# SW6106_A_A_B_C_Lighting_MCU_SEG.net
KiCad netlist of a schematic drawn in Altium Designer
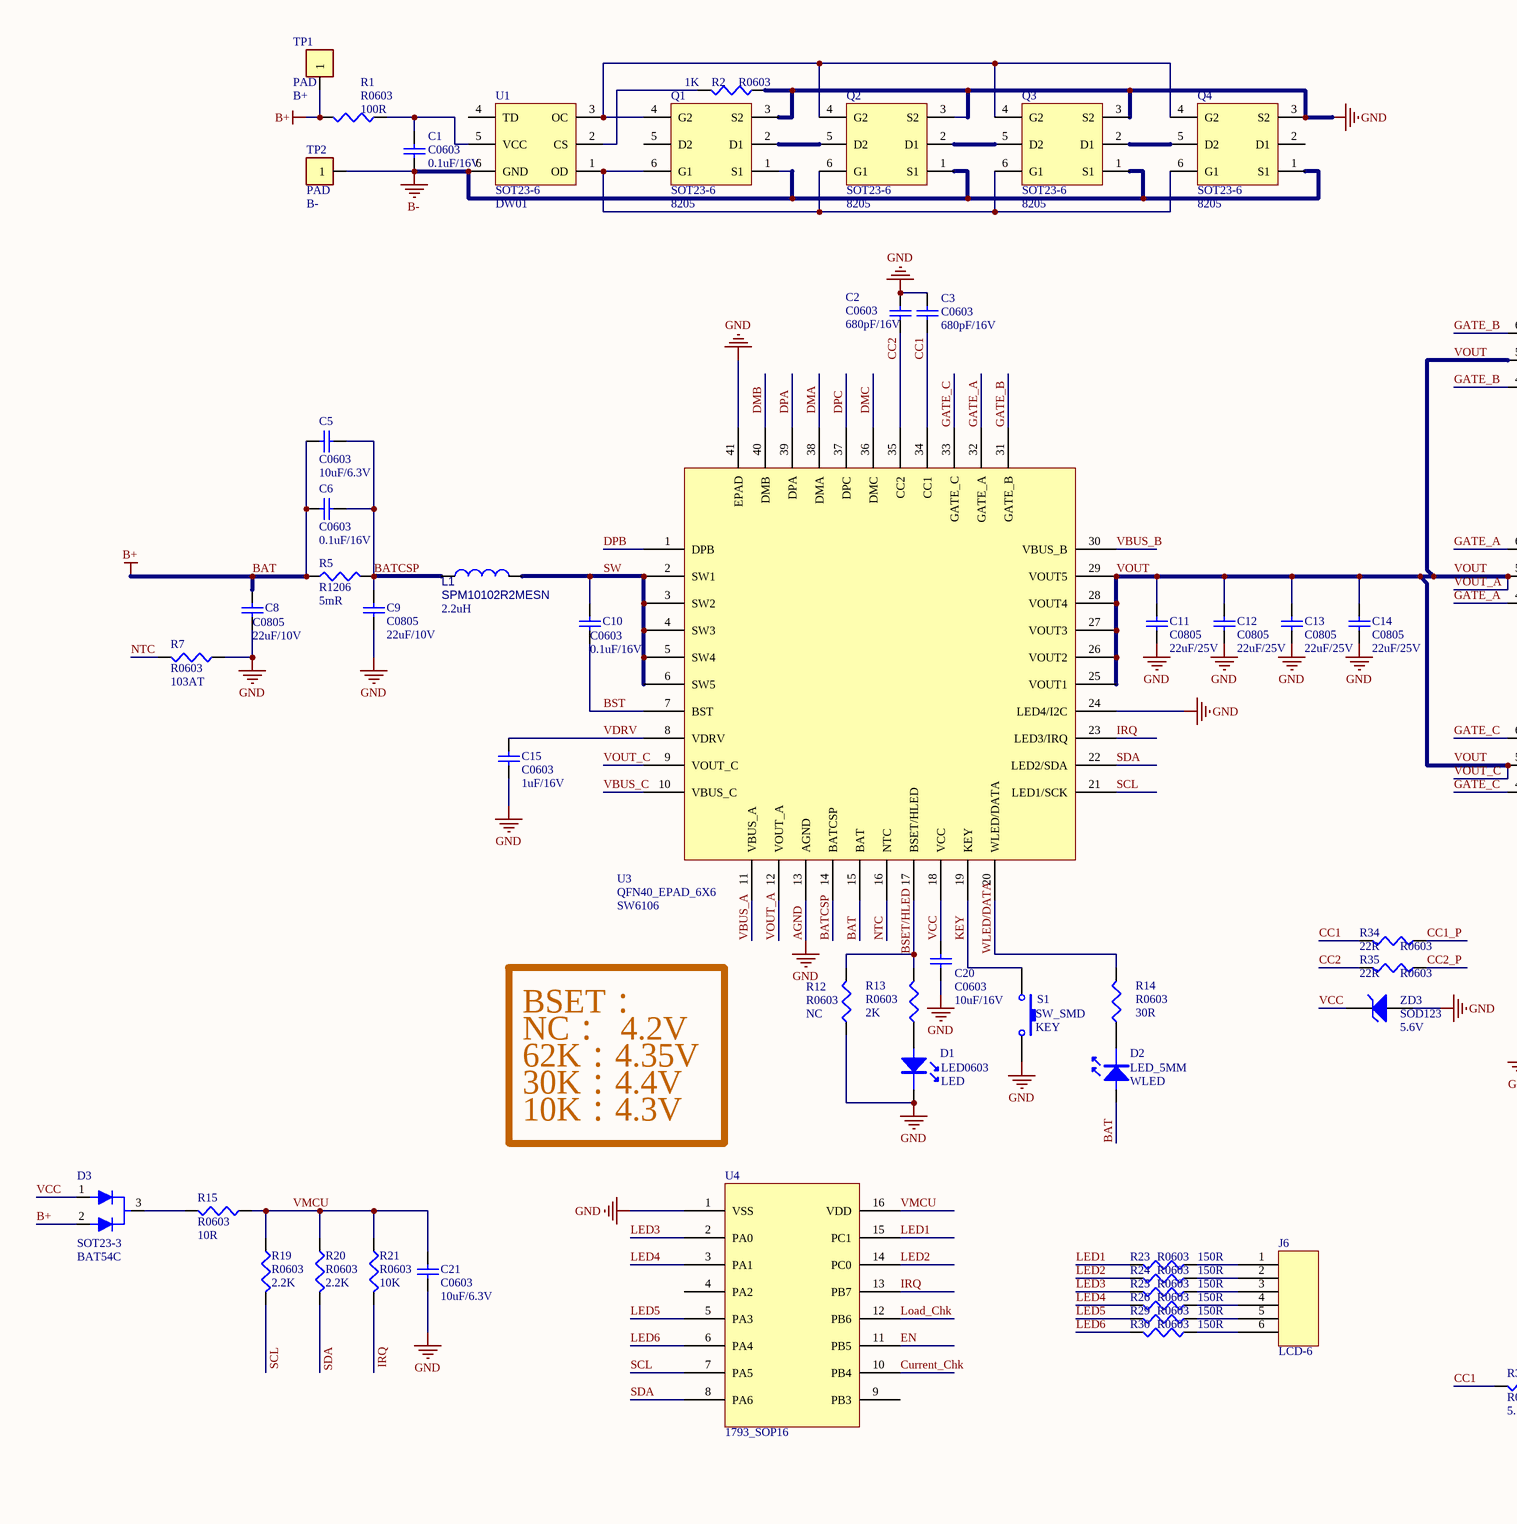
[diagram p0: SW6106+A+A+B+C+Lighting+MCU+SEG.SchDoc, left]
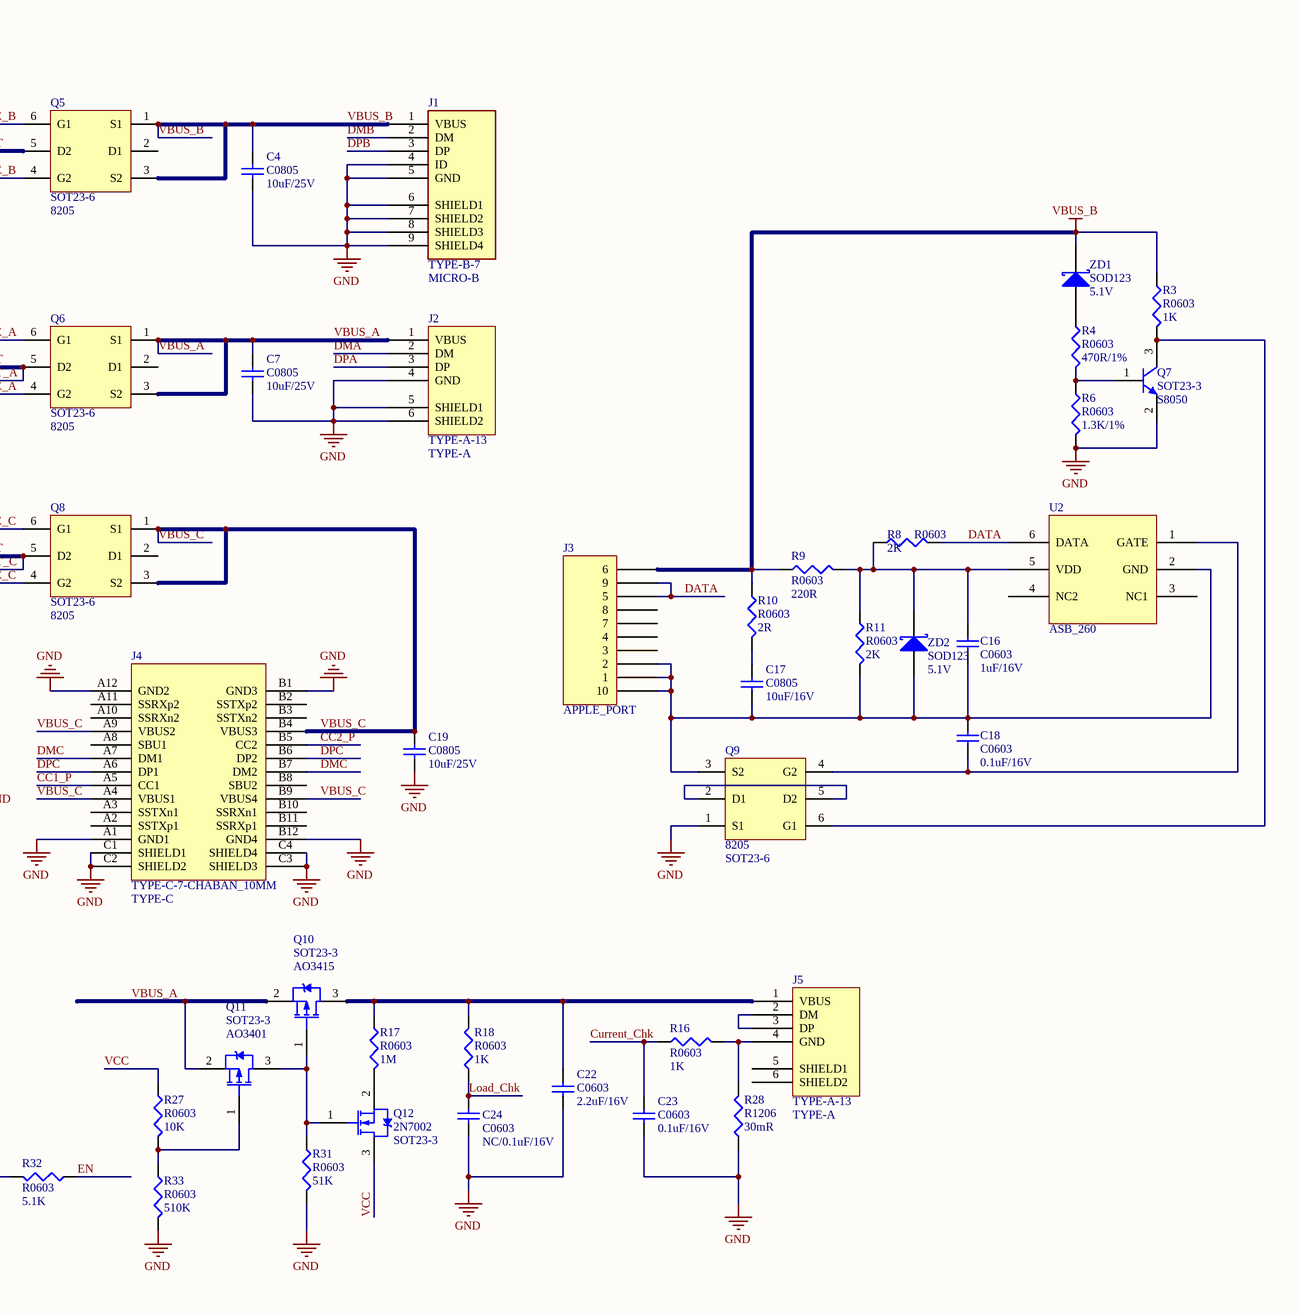
[diagram p1: SW6106+A+A+B+C+Lighting+MCU+SEG.SchDoc, right]

(export (version "E")
  (design (tool "Eeschema 10.0.6"))
  (components
    (comp (ref "C1")
      (value "C0603")
      (footprint "C0603")
      (description "Capacitor")
      (fields (field (name "ALTIUM_VALUE") "0.1uF/16V") (field (name "PUBLISHER") "Altium Limited"))
      (libsource (lib "*") (part "Cap"))
    )
    (comp (ref "C2")
      (value "C0603")
      (footprint "C0603")
      (description "Capacitor")
      (fields (field (name "ALTIUM_VALUE") "680pF/16V") (field (name "PUBLISHER") "Altium Limited"))
      (libsource (lib "*") (part "CAP0603"))
    )
    (comp (ref "C3")
      (value "C0603")
      (footprint "C0603")
      (description "Capacitor")
      (fields (field (name "ALTIUM_VALUE") "680pF/16V") (field (name "PUBLISHER") "Altium Limited"))
      (libsource (lib "*") (part "CAP0603"))
    )
    (comp (ref "C4")
      (value "C0805")
      (footprint "C0805")
      (description "Capacitor")
      (fields (field (name "ALTIUM_VALUE") "10uF/25V") (field (name "PUBLISHER") "Altium Limited"))
      (libsource (lib "*") (part "CAP0603"))
    )
    (comp (ref "C5")
      (value "C0603")
      (footprint "C0603")
      (description "Capacitor")
      (fields (field (name "ALTIUM_VALUE") "10uF/6.3V") (field (name "PUBLISHER") "Altium Limited"))
      (libsource (lib "*") (part "CAP0603"))
    )
    (comp (ref "C6")
      (value "C0603")
      (footprint "C0603")
      (description "Capacitor")
      (fields (field (name "ALTIUM_VALUE") "0.1uF/16V") (field (name "PUBLISHER") "Altium Limited"))
      (libsource (lib "*") (part "CAP0603"))
    )
    (comp (ref "C7")
      (value "C0805")
      (footprint "C0805")
      (description "Capacitor")
      (fields (field (name "ALTIUM_VALUE") "10uF/25V") (field (name "PUBLISHER") "Altium Limited"))
      (libsource (lib "*") (part "CAP0603"))
    )
    (comp (ref "C8")
      (value "C0805")
      (footprint "C0805")
      (description "Capacitor")
      (fields (field (name "ALTIUM_VALUE") "22uF/10V") (field (name "PUBLISHER") "Altium Limited"))
      (libsource (lib "*") (part "CAP0805"))
    )
    (comp (ref "C9")
      (value "C0805")
      (footprint "C0805")
      (description "Capacitor")
      (fields (field (name "ALTIUM_VALUE") "22uF/10V") (field (name "PUBLISHER") "Altium Limited"))
      (libsource (lib "*") (part "CAP0805"))
    )
    (comp (ref "C10")
      (value "C0603")
      (footprint "C0603")
      (description "Capacitor")
      (fields (field (name "ALTIUM_VALUE") "0.1uF/16V") (field (name "PUBLISHER") "Altium Limited"))
      (libsource (lib "*") (part "CAP0603"))
    )
    (comp (ref "C11")
      (value "C0805")
      (footprint "C0805")
      (description "Capacitor")
      (fields (field (name "ALTIUM_VALUE") "22uF/25V") (field (name "PUBLISHER") "Altium Limited"))
      (libsource (lib "*") (part "CAP0805"))
    )
    (comp (ref "C12")
      (value "C0805")
      (footprint "C0805")
      (description "Capacitor")
      (fields (field (name "ALTIUM_VALUE") "22uF/25V") (field (name "PUBLISHER") "Altium Limited"))
      (libsource (lib "*") (part "CAP0805"))
    )
    (comp (ref "C13")
      (value "C0805")
      (footprint "C0805")
      (description "Capacitor")
      (fields (field (name "ALTIUM_VALUE") "22uF/25V") (field (name "PUBLISHER") "Altium Limited"))
      (libsource (lib "*") (part "CAP0805"))
    )
    (comp (ref "C14")
      (value "C0805")
      (footprint "C0805")
      (description "Capacitor")
      (fields (field (name "ALTIUM_VALUE") "22uF/25V") (field (name "PUBLISHER") "Altium Limited"))
      (libsource (lib "*") (part "CAP0805"))
    )
    (comp (ref "C15")
      (value "C0603")
      (footprint "C0603")
      (description "Capacitor")
      (fields (field (name "ALTIUM_VALUE") "1uF/16V") (field (name "PUBLISHER") "Altium Limited"))
      (libsource (lib "*") (part "CAP0603"))
    )
    (comp (ref "C16")
      (value "C0603")
      (footprint "C0603")
      (description "Capacitor")
      (fields (field (name "ALTIUM_VALUE") "1uF/16V") (field (name "PUBLISHER") "Altium Limited"))
      (libsource (lib "*") (part "CAP0805"))
    )
    (comp (ref "C17")
      (value "C0805")
      (footprint "C0805")
      (description "Capacitor")
      (fields (field (name "ALTIUM_VALUE") "10uF/16V") (field (name "PUBLISHER") "Altium Limited"))
      (libsource (lib "*") (part "CAP0805"))
    )
    (comp (ref "C18")
      (value "C0603")
      (footprint "C0603")
      (description "Capacitor")
      (fields (field (name "ALTIUM_VALUE") "0.1uF/16V") (field (name "PUBLISHER") "Altium Limited"))
      (libsource (lib "*") (part "CAP0805"))
    )
    (comp (ref "C19")
      (value "C0805")
      (footprint "C0805")
      (description "Capacitor")
      (fields (field (name "ALTIUM_VALUE") "10uF/25V") (field (name "PUBLISHER") "Altium Limited"))
      (libsource (lib "*") (part "CAP0603"))
    )
    (comp (ref "C20")
      (value "C0603")
      (footprint "C0603")
      (description "Capacitor")
      (fields (field (name "ALTIUM_VALUE") "10uF/16V") (field (name "PUBLISHER") "Altium Limited"))
      (libsource (lib "*") (part "CAP0603"))
    )
    (comp (ref "C21")
      (value "C0603")
      (footprint "C0603")
      (description "Capacitor")
      (fields (field (name "ALTIUM_VALUE") "10uF/6.3V") (field (name "PUBLISHER") "Altium Limited"))
      (libsource (lib "*") (part "CAP0603"))
    )
    (comp (ref "C22")
      (value "C0603")
      (footprint "C0603")
      (description "Capacitor")
      (fields (field (name "ALTIUM_VALUE") "2.2uF/16V") (field (name "PUBLISHER") "Altium Limited"))
      (libsource (lib "*") (part "CAP0603"))
    )
    (comp (ref "C23")
      (value "C0603")
      (footprint "C0603")
      (description "Capacitor")
      (fields (field (name "ALTIUM_VALUE") "0.1uF/16V") (field (name "PUBLISHER") "Altium Limited"))
      (libsource (lib "*") (part "CAP0603"))
    )
    (comp (ref "C24")
      (value "C0603")
      (footprint "C0603")
      (description "Capacitor")
      (fields (field (name "ALTIUM_VALUE") "NC/0.1uF/16V") (field (name "PUBLISHER") "Altium Limited"))
      (libsource (lib "*") (part "CAP0603"))
    )
    (comp (ref "D1") (value "LED") (footprint "LED0603") (libsource (lib "*") (part "LED")))
    (comp (ref "D2")
      (value "WLED")
      (footprint "LED_5MM")
      (fields (field (name "FOOTPRINF") "LED_5MM") (field (name "Comment") "LED_5MM"))
      (libsource (lib "*") (part "LED"))
    )
    (comp (ref "D3") (value "BAT54C") (footprint "SOT23-3") (libsource (lib "Schlib1-2012") (part "D3")))
    (comp (ref "J1")
      (value "MICRO-B")
      (footprint "TYPE-B-7")
      (fields (field (name "FOOTPRINTF") "TYPE-B-7") (field (name "Comment") "USB_MICRO_B"))
      (libsource (lib "*") (part "USB_MICRO_B"))
    )
    (comp (ref "J2")
      (value "TYPE-A")
      (footprint "TYPE-A-13")
      (fields (field (name "FOOTPRINF") "TYPE-A-13") (field (name "Comment") "TYPE-A-1"))
      (libsource (lib "*") (part "TYPE-A-1"))
    )
    (comp (ref "J3") (value "APPLE_PORT") (libsource (lib "TEST") (part "APPLE_PORT")))
    (comp (ref "J4")
      (value "TYPE-C")
      (footprint "TYPE-C-7-CHABAN_10MM")
      (libsource (lib "*") (part "TYPE-C"))
    )
    (comp (ref "J5")
      (value "TYPE-A")
      (footprint "PIE10-USB")
      (fields (field (name "FOOTPRINF") "TYPE-A-13") (field (name "Comment") "TYPE-A-1"))
      (libsource (lib "*") (part "TYPE-A-1"))
    )
    (comp (ref "J6") (value "LCD-6") (libsource (lib "TEST") (part "LCD-6")))
    (comp (ref "L1")
      (value "SPM10102R2MESN")
      (footprint "INDUCTOR_SPM1010")
      (fields (field (name "ALTIUM_VALUE") "2.2uH"))
      (libsource (lib "*") (part "INDUCTOR"))
    )
    (comp (ref "Q1")
      (value "8205")
      (footprint "SOT23-6")
      (fields (field (name "FOOTPRINF") "SOT23-6"))
      (libsource (lib "*") (part "8205B"))
    )
    (comp (ref "Q2")
      (value "8205")
      (footprint "SOT23-6")
      (fields (field (name "FOOTPRINF") "SOT23-6"))
      (libsource (lib "*") (part "8205B"))
    )
    (comp (ref "Q3")
      (value "8205")
      (footprint "SOT23-6")
      (fields (field (name "FOOTPRINF") "SOT23-6"))
      (libsource (lib "*") (part "8205B"))
    )
    (comp (ref "Q4")
      (value "8205")
      (footprint "SOT23-6")
      (fields (field (name "FOOTPRINF") "SOT23-6"))
      (libsource (lib "*") (part "8205B"))
    )
    (comp (ref "Q5")
      (value "8205")
      (footprint "SOT23-6")
      (fields (field (name "FOOTPRINF") "SOT23-6"))
      (libsource (lib "") (part "8205B_1"))
    )
    (comp (ref "Q6")
      (value "8205")
      (footprint "SOT23-6")
      (fields (field (name "FOOTPRINF") "SOT23-6"))
      (libsource (lib "") (part "8205B_1"))
    )
    (comp (ref "Q7")
      (value "S8050")
      (footprint "SOT23-3")
      (description "NPN General Purpose Amplifier")
      (fields (field (name "PUBLISHER") "Altium Limited"))
      (libsource (lib "Miscellaneous Devices") (part "2N3904"))
    )
    (comp (ref "Q8")
      (value "8205")
      (footprint "SOT23-6")
      (fields (field (name "FOOTPRINF") "SOT23-6"))
      (libsource (lib "") (part "8205B_1"))
    )
    (comp (ref "Q9")
      (value "8205")
      (footprint "SOT23-6")
      (fields (field (name "FOOTPRINF") "SOT23-6"))
      (libsource (lib "") (part "8205B_2"))
    )
    (comp (ref "Q10")
      (value "AO3415")
      (footprint "SOT23-3")
      (description "P-Channel Power MOSFET")
      (fields (field (name "Comment") "PMOS-2") (field (name "PUBLISHER") "Altium Limited"))
      (libsource (lib "Miscellaneous Devices") (part "PMOS-2"))
    )
    (comp (ref "Q11")
      (value "AO3401")
      (footprint "SOT23-3")
      (description "P-Channel Power MOSFET")
      (fields (field (name "Comment") "PMOS-2") (field (name "PUBLISHER") "Altium Limited"))
      (libsource (lib "Miscellaneous Devices") (part "PMOS-2"))
    )
    (comp (ref "Q12")
      (value "2N7002")
      (footprint "SOT23-3")
      (description "N-Channel Power MOSFET")
      (fields (field (name "Comment") "NMOS-2") (field (name "PUBLISHER") "Altium Limited"))
      (libsource (lib "Miscellaneous Devices") (part "NMOS-2"))
    )
    (comp (ref "R1")
      (value "R0603")
      (footprint "R0603")
      (description "Resistor")
      (fields (field (name "ALTIUM_VALUE") "100R") (field (name "PUBLISHER") "Altium Limited"))
      (libsource (lib "*") (part "Res3"))
    )
    (comp (ref "R2")
      (value "R0603")
      (footprint "R0603")
      (description "Resistor")
      (fields (field (name "ALTIUM_VALUE") "1K") (field (name "PUBLISHER") "Altium Limited"))
      (libsource (lib "*") (part "Res3"))
    )
    (comp (ref "R3")
      (value "R0603")
      (footprint "R0603")
      (description "Resistor")
      (fields (field (name "ALTIUM_VALUE") "1K") (field (name "PUBLISHER") "Altium Limited"))
      (libsource (lib "Miscellaneous Devices") (part "Res3"))
    )
    (comp (ref "R4")
      (value "R0603")
      (footprint "R0603")
      (description "Resistor")
      (fields (field (name "ALTIUM_VALUE") "470R/1%") (field (name "PUBLISHER") "Altium Limited"))
      (libsource (lib "Miscellaneous Devices") (part "Res3"))
    )
    (comp (ref "R5")
      (value "R1206")
      (footprint "R1206")
      (description "Resistor")
      (fields (field (name "ALTIUM_VALUE") "5mR") (field (name "PUBLISHER") "Altium Limited"))
      (libsource (lib "*") (part "RES"))
    )
    (comp (ref "R6")
      (value "R0603")
      (footprint "R0603")
      (description "Resistor")
      (fields (field (name "ALTIUM_VALUE") "1.3K/1%") (field (name "PUBLISHER") "Altium Limited"))
      (libsource (lib "Miscellaneous Devices") (part "Res3"))
    )
    (comp (ref "R7")
      (value "R0603")
      (footprint "R0603")
      (description "Resistor")
      (fields (field (name "ALTIUM_VALUE") "103AT") (field (name "PUBLISHER") "Altium Limited"))
      (libsource (lib "*") (part "RES"))
    )
    (comp (ref "R8")
      (value "R0603")
      (footprint "R0603")
      (description "Resistor")
      (fields (field (name "ALTIUM_VALUE") "2K") (field (name "PUBLISHER") "Altium Limited"))
      (libsource (lib "Miscellaneous Devices") (part "Res3"))
    )
    (comp (ref "R9")
      (value "R0603")
      (footprint "R0603")
      (description "Resistor")
      (fields (field (name "ALTIUM_VALUE") "220R") (field (name "PUBLISHER") "Altium Limited"))
      (libsource (lib "Miscellaneous Devices") (part "Res3"))
    )
    (comp (ref "R10")
      (value "R0603")
      (footprint "R0603")
      (description "Resistor")
      (fields (field (name "ALTIUM_VALUE") "2R") (field (name "PUBLISHER") "Altium Limited"))
      (libsource (lib "Miscellaneous Devices") (part "Res3"))
    )
    (comp (ref "R11")
      (value "R0603")
      (footprint "R0603")
      (description "Resistor")
      (fields (field (name "ALTIUM_VALUE") "2K") (field (name "PUBLISHER") "Altium Limited"))
      (libsource (lib "Miscellaneous Devices") (part "Res3"))
    )
    (comp (ref "R12")
      (value "R0603")
      (footprint "R0603")
      (description "Resistor")
      (fields (field (name "ALTIUM_VALUE") "NC") (field (name "PUBLISHER") "Altium Limited"))
      (libsource (lib "*") (part "RES"))
    )
    (comp (ref "R13")
      (value "R0603")
      (footprint "R0603")
      (description "Resistor")
      (fields (field (name "ALTIUM_VALUE") "2K") (field (name "PUBLISHER") "Altium Limited"))
      (libsource (lib "*") (part "RES"))
    )
    (comp (ref "R14")
      (value "R0603")
      (footprint "R0603")
      (description "Resistor")
      (fields (field (name "ALTIUM_VALUE") "30R") (field (name "PUBLISHER") "Altium Limited"))
      (libsource (lib "*") (part "RES"))
    )
    (comp (ref "R15")
      (value "R0603")
      (footprint "R0603")
      (description "Resistor")
      (fields (field (name "ALTIUM_VALUE") "10R") (field (name "PUBLISHER") "Altium Limited"))
      (libsource (lib "*") (part "RES"))
    )
    (comp (ref "R16")
      (value "R0603")
      (footprint "R0603")
      (description "Resistor")
      (fields (field (name "ALTIUM_VALUE") "1K") (field (name "PUBLISHER") "Altium Limited"))
      (libsource (lib "*") (part "RES"))
    )
    (comp (ref "R17")
      (value "R0603")
      (footprint "R0603")
      (description "Resistor")
      (fields (field (name "ALTIUM_VALUE") "1M") (field (name "PUBLISHER") "Altium Limited"))
      (libsource (lib "*") (part "RES"))
    )
    (comp (ref "R18")
      (value "R0603")
      (footprint "R0603")
      (description "Resistor")
      (fields (field (name "ALTIUM_VALUE") "1K") (field (name "PUBLISHER") "Altium Limited"))
      (libsource (lib "*") (part "RES"))
    )
    (comp (ref "R19")
      (value "R0603")
      (footprint "R0603")
      (description "Resistor")
      (fields (field (name "ALTIUM_VALUE") "2.2K") (field (name "PUBLISHER") "Altium Limited"))
      (libsource (lib "*") (part "RES"))
    )
    (comp (ref "R20")
      (value "R0603")
      (footprint "R0603")
      (description "Resistor")
      (fields (field (name "ALTIUM_VALUE") "2.2K") (field (name "PUBLISHER") "Altium Limited"))
      (libsource (lib "*") (part "RES"))
    )
    (comp (ref "R21")
      (value "R0603")
      (footprint "R0603")
      (description "Resistor")
      (fields (field (name "ALTIUM_VALUE") "10K") (field (name "PUBLISHER") "Altium Limited"))
      (libsource (lib "*") (part "RES"))
    )
    (comp (ref "R23")
      (value "R0603")
      (footprint "R0603")
      (description "Resistor")
      (fields (field (name "ALTIUM_VALUE") "150R") (field (name "PUBLISHER") "Altium Limited"))
      (libsource (lib "*") (part "RES"))
    )
    (comp (ref "R24")
      (value "R0603")
      (footprint "R0603")
      (description "Resistor")
      (fields (field (name "ALTIUM_VALUE") "150R") (field (name "PUBLISHER") "Altium Limited"))
      (libsource (lib "*") (part "RES"))
    )
    (comp (ref "R25")
      (value "R0603")
      (footprint "R0603")
      (description "Resistor")
      (fields (field (name "ALTIUM_VALUE") "150R") (field (name "PUBLISHER") "Altium Limited"))
      (libsource (lib "*") (part "RES"))
    )
    (comp (ref "R26")
      (value "R0603")
      (footprint "R0603")
      (description "Resistor")
      (fields (field (name "ALTIUM_VALUE") "150R") (field (name "PUBLISHER") "Altium Limited"))
      (libsource (lib "*") (part "RES"))
    )
    (comp (ref "R27")
      (value "R0603")
      (footprint "R0603")
      (description "Resistor")
      (fields (field (name "ALTIUM_VALUE") "10K") (field (name "PUBLISHER") "Altium Limited"))
      (libsource (lib "*") (part "RES"))
    )
    (comp (ref "R28")
      (value "R1206")
      (footprint "C-1206A")
      (description "Resistor")
      (fields (field (name "ALTIUM_VALUE") "30mR") (field (name "PUBLISHER") "Altium Limited"))
      (libsource (lib "*") (part "RES"))
    )
    (comp (ref "R29")
      (value "R0603")
      (footprint "R0603")
      (description "Resistor")
      (fields (field (name "ALTIUM_VALUE") "150R") (field (name "PUBLISHER") "Altium Limited"))
      (libsource (lib "*") (part "RES"))
    )
    (comp (ref "R30")
      (value "R0603")
      (footprint "R0603")
      (description "Resistor")
      (fields (field (name "ALTIUM_VALUE") "150R") (field (name "PUBLISHER") "Altium Limited"))
      (libsource (lib "*") (part "RES"))
    )
    (comp (ref "R31")
      (value "R0603")
      (footprint "R0603")
      (description "Resistor")
      (fields (field (name "ALTIUM_VALUE") "51K") (field (name "PUBLISHER") "Altium Limited"))
      (libsource (lib "*") (part "RES"))
    )
    (comp (ref "R32")
      (value "R0603")
      (footprint "R0603")
      (description "Resistor")
      (fields (field (name "ALTIUM_VALUE") "5.1K") (field (name "PUBLISHER") "Altium Limited"))
      (libsource (lib "*") (part "RES"))
    )
    (comp (ref "R33")
      (value "R0603")
      (footprint "R0603")
      (description "Resistor")
      (fields (field (name "ALTIUM_VALUE") "510K") (field (name "PUBLISHER") "Altium Limited"))
      (libsource (lib "*") (part "RES"))
    )
    (comp (ref "R34")
      (value "R0603")
      (footprint "R0603")
      (description "Resistor")
      (fields (field (name "ALTIUM_VALUE") "22R") (field (name "PUBLISHER") "Altium Limited"))
      (libsource (lib "*") (part "RES"))
    )
    (comp (ref "R35")
      (value "R0603")
      (footprint "R0603")
      (description "Resistor")
      (fields (field (name "ALTIUM_VALUE") "22R") (field (name "PUBLISHER") "Altium Limited"))
      (libsource (lib "*") (part "RES"))
    )
    (comp (ref "S1")
      (value "KEY")
      (footprint "SW_SMD")
      (fields (field (name "FOOTPRINF") "SW_SMD"))
      (libsource (lib "*") (part "SW K"))
    )
    (comp (ref "TP1") (value "B+") (footprint "PAD") (libsource (lib "") (part "Test Point_1")))
    (comp (ref "TP2") (value "B-") (footprint "PAD") (libsource (lib "*") (part "Test Point")))
    (comp (ref "U1")
      (value "DW01")
      (footprint "SOT23-6")
      (fields (field (name "FOOTPRINF") "SOT23-6"))
      (libsource (lib "*") (part "DW01"))
    )
    (comp (ref "U2") (value "ASB_260") (footprint "SOT-23-") (libsource (lib "TEST") (part "ASB_260")))
    (comp (ref "U3")
      (value "SW6106")
      (footprint "QFN40_EPAD_6X6")
      (libsource (lib "TEST") (part "SW6106_AFC"))
    )
    (comp (ref "U4") (value "1793_SOP16") (libsource (lib "TEST") (part "1793_SOP16")))
    (comp (ref "ZD1")
      (value "5.1V")
      (footprint "SOD123")
      (description "Schottky Rectifier")
      (fields (field (name "Comment") "Diode 11DQ03") (field (name "PUBLISHER") "Altium Limited"))
      (libsource (lib "Miscellaneous Devices") (part "Diode 11DQ03"))
    )
    (comp (ref "ZD2")
      (value "5.1V")
      (footprint "SOD123")
      (description "Schottky Rectifier")
      (fields (field (name "Comment") "Diode 11DQ03") (field (name "PUBLISHER") "Altium Limited"))
      (libsource (lib "Miscellaneous Devices") (part "Diode 11DQ03"))
    )
    (comp (ref "ZD3")
      (value "SOD123")
      (footprint "SOD-123")
      (description "Zener Diode")
      (fields (field (name "ALTIUM_UNNAMED_1") "5.6V"))
      (libsource (lib "Miscellaneous Devices") (part "D Zener"))
    )
  )
  (nets
    (net (code "1") (name "/BATCSP") (class "Default")
      (node (ref "C5") (pin "2") (pinfunction "2_2") (pintype "passive"))
      (node (ref "C6") (pin "2") (pinfunction "2_2") (pintype "passive"))
      (node (ref "C9") (pin "2") (pinfunction "2_2") (pintype "passive"))
      (node (ref "L1") (pin "1") (pinfunction "1_1") (pintype "passive"))
      (node (ref "R5") (pin "2") (pinfunction "2_2") (pintype "passive"))
      (node (ref "U3") (pin "14") (pinfunction "BATCSP_14") (pintype "passive"))
    )
    (net (code "2") (name "/BSET{slash}HLED") (class "Default")
      (node (ref "R12") (pin "2") (pinfunction "2_2") (pintype "passive"))
      (node (ref "R13") (pin "2") (pinfunction "2_2") (pintype "passive"))
      (node (ref "U3") (pin "17") (pinfunction "BSET/HLED_17") (pintype "passive"))
    )
    (net (code "3") (name "/BST") (class "Default")
      (node (ref "C10") (pin "1") (pinfunction "1_1") (pintype "passive"))
      (node (ref "U3") (pin "7") (pinfunction "BST_7") (pintype "passive"))
    )
    (net (code "4") (name "/CC1") (class "Default")
      (node (ref "C3") (pin "1") (pinfunction "1_1") (pintype "passive"))
      (node (ref "R32") (pin "2") (pinfunction "2_2") (pintype "passive"))
      (node (ref "R34") (pin "2") (pinfunction "2_2") (pintype "passive"))
      (node (ref "U3") (pin "34") (pinfunction "CC1_34") (pintype "passive"))
    )
    (net (code "5") (name "/CC1_P") (class "Default")
      (node (ref "J4") (pin "A5") (pinfunction "CC1_A5") (pintype "passive"))
      (node (ref "R34") (pin "1") (pinfunction "1_1") (pintype "passive"))
    )
    (net (code "6") (name "/CC2") (class "Default")
      (node (ref "C2") (pin "1") (pinfunction "1_1") (pintype "passive"))
      (node (ref "R35") (pin "2") (pinfunction "2_2") (pintype "passive"))
      (node (ref "U3") (pin "35") (pinfunction "CC2_35") (pintype "passive"))
    )
    (net (code "7") (name "/CC2_P") (class "Default")
      (node (ref "J4") (pin "B5") (pinfunction "CC2_B5") (pintype "passive"))
      (node (ref "R35") (pin "1") (pinfunction "1_1") (pintype "passive"))
    )
    (net (code "8") (name "/Current_Chk") (class "Default")
      (node (ref "C23") (pin "2") (pinfunction "2_2") (pintype "passive"))
      (node (ref "R16") (pin "1") (pinfunction "1_1") (pintype "passive"))
      (node (ref "U4") (pin "10") (pinfunction "PB4_10") (pintype "passive"))
    )
    (net (code "9") (name "/DATA") (class "Default")
      (node (ref "J3") (pin "5") (pinfunction "5_5") (pintype "passive"))
      (node (ref "J3") (pin "9") (pinfunction "9_9") (pintype "passive"))
      (node (ref "R8") (pin "2") (pinfunction "2_2") (pintype "passive"))
      (node (ref "U2") (pin "6") (pinfunction "DATA_6") (pintype "passive"))
    )
    (net (code "10") (name "/DMA") (class "Default")
      (node (ref "J2") (pin "2") (pinfunction "DM_2") (pintype "passive"))
      (node (ref "U3") (pin "38") (pinfunction "DMA_38") (pintype "passive"))
    )
    (net (code "11") (name "/DMB") (class "Default")
      (node (ref "J1") (pin "2") (pinfunction "DM_2") (pintype "passive"))
      (node (ref "U3") (pin "40") (pinfunction "DMB_40") (pintype "passive"))
    )
    (net (code "12") (name "/DMC") (class "Default")
      (node (ref "J4") (pin "A7") (pinfunction "DM1_A7") (pintype "passive"))
      (node (ref "J4") (pin "B7") (pinfunction "DM2_B7") (pintype "passive"))
      (node (ref "U3") (pin "36") (pinfunction "DMC_36") (pintype "passive"))
    )
    (net (code "13") (name "/DPA") (class "Default")
      (node (ref "J2") (pin "3") (pinfunction "DP_3") (pintype "passive"))
      (node (ref "U3") (pin "39") (pinfunction "DPA_39") (pintype "passive"))
    )
    (net (code "14") (name "/DPB") (class "Default")
      (node (ref "J1") (pin "3") (pinfunction "DP_3") (pintype "passive"))
      (node (ref "U3") (pin "1") (pinfunction "DPB_1") (pintype "passive"))
    )
    (net (code "15") (name "/DPC") (class "Default")
      (node (ref "J4") (pin "A6") (pinfunction "DP1_A6") (pintype "passive"))
      (node (ref "J4") (pin "B6") (pinfunction "DP2_B6") (pintype "passive"))
      (node (ref "U3") (pin "37") (pinfunction "DPC_37") (pintype "passive"))
    )
    (net (code "16") (name "/EN") (class "Default")
      (node (ref "R32") (pin "1") (pinfunction "1_1") (pintype "passive"))
      (node (ref "U4") (pin "11") (pinfunction "PB5_11") (pintype "passive"))
    )
    (net (code "17") (name "/GATE_A") (class "Default")
      (node (ref "Q6") (pin "4") (pinfunction "G2_4") (pintype "passive"))
      (node (ref "Q6") (pin "6") (pinfunction "G1_6") (pintype "passive"))
      (node (ref "U3") (pin "32") (pinfunction "GATE_A_32") (pintype "passive"))
    )
    (net (code "18") (name "/GATE_B") (class "Default")
      (node (ref "Q5") (pin "4") (pinfunction "G2_4") (pintype "passive"))
      (node (ref "Q5") (pin "6") (pinfunction "G1_6") (pintype "passive"))
      (node (ref "U3") (pin "31") (pinfunction "GATE_B_31") (pintype "passive"))
    )
    (net (code "19") (name "/GATE_C") (class "Default")
      (node (ref "Q8") (pin "4") (pinfunction "G2_4") (pintype "passive"))
      (node (ref "Q8") (pin "6") (pinfunction "G1_6") (pintype "passive"))
      (node (ref "U3") (pin "33") (pinfunction "GATE_C_33") (pintype "passive"))
    )
    (net (code "20") (name "/IRQ") (class "Default")
      (node (ref "R21") (pin "2") (pinfunction "2_2") (pintype "passive"))
      (node (ref "U3") (pin "23") (pinfunction "LED3/IRQ_23") (pintype "passive"))
      (node (ref "U4") (pin "13") (pinfunction "PB7_13") (pintype "passive"))
    )
    (net (code "21") (name "/KEY") (class "Default")
      (node (ref "S1") (pin "1") (pinfunction "1_1") (pintype "passive"))
      (node (ref "U3") (pin "19") (pinfunction "KEY_19") (pintype "passive"))
    )
    (net (code "22") (name "/LED1") (class "Default")
      (node (ref "R23") (pin "2") (pinfunction "2_2") (pintype "passive"))
      (node (ref "U4") (pin "15") (pinfunction "PC1_15") (pintype "passive"))
    )
    (net (code "23") (name "/LED2") (class "Default")
      (node (ref "R24") (pin "2") (pinfunction "2_2") (pintype "passive"))
      (node (ref "U4") (pin "14") (pinfunction "PC0_14") (pintype "passive"))
    )
    (net (code "24") (name "/LED3") (class "Default")
      (node (ref "R25") (pin "2") (pinfunction "2_2") (pintype "passive"))
      (node (ref "U4") (pin "2") (pinfunction "PA0_2") (pintype "passive"))
    )
    (net (code "25") (name "/LED4") (class "Default")
      (node (ref "R26") (pin "2") (pinfunction "2_2") (pintype "passive"))
      (node (ref "U4") (pin "3") (pinfunction "PA1_3") (pintype "passive"))
    )
    (net (code "26") (name "/LED5") (class "Default")
      (node (ref "R29") (pin "2") (pinfunction "2_2") (pintype "passive"))
      (node (ref "U4") (pin "5") (pinfunction "PA3_5") (pintype "passive"))
    )
    (net (code "27") (name "/LED6") (class "Default")
      (node (ref "R30") (pin "2") (pinfunction "2_2") (pintype "passive"))
      (node (ref "U4") (pin "6") (pinfunction "PA4_6") (pintype "passive"))
    )
    (net (code "28") (name "/Load_Chk") (class "Default")
      (node (ref "C24") (pin "2") (pinfunction "2_2") (pintype "passive"))
      (node (ref "R18") (pin "1") (pinfunction "1_1") (pintype "passive"))
      (node (ref "U4") (pin "12") (pinfunction "PB6_12") (pintype "passive"))
    )
    (net (code "29") (name "/NTC") (class "Default")
      (node (ref "R7") (pin "2") (pinfunction "2_2") (pintype "passive"))
      (node (ref "U3") (pin "16") (pinfunction "NTC_16") (pintype "passive"))
    )
    (net (code "30") (name "/SCL") (class "Default")
      (node (ref "R19") (pin "2") (pinfunction "2_2") (pintype "passive"))
      (node (ref "U3") (pin "21") (pinfunction "LED1/SCK_21") (pintype "passive"))
      (node (ref "U4") (pin "7") (pinfunction "PA5_7") (pintype "passive"))
    )
    (net (code "31") (name "/SDA") (class "Default")
      (node (ref "R20") (pin "2") (pinfunction "2_2") (pintype "passive"))
      (node (ref "U3") (pin "22") (pinfunction "LED2/SDA_22") (pintype "passive"))
      (node (ref "U4") (pin "8") (pinfunction "PA6_8") (pintype "passive"))
    )
    (net (code "32") (name "/SW") (class "Default")
      (node (ref "C10") (pin "2") (pinfunction "2_2") (pintype "passive"))
      (node (ref "L1") (pin "2") (pinfunction "2_2") (pintype "passive"))
      (node (ref "U3") (pin "2") (pinfunction "SW1_2") (pintype "passive"))
      (node (ref "U3") (pin "3") (pinfunction "SW2_3") (pintype "passive"))
      (node (ref "U3") (pin "4") (pinfunction "SW3_4") (pintype "passive"))
      (node (ref "U3") (pin "5") (pinfunction "SW4_5") (pintype "passive"))
      (node (ref "U3") (pin "6") (pinfunction "SW5_6") (pintype "passive"))
    )
    (net (code "33") (name "/VBUS_A") (class "Default")
      (node (ref "C7") (pin "2") (pinfunction "2_2") (pintype "passive"))
      (node (ref "J2") (pin "1") (pinfunction "VBUS_1") (pintype "passive"))
      (node (ref "Q10") (pin "2") (pinfunction "S_2") (pintype "passive"))
      (node (ref "Q11") (pin "2") (pinfunction "S_2") (pintype "passive"))
      (node (ref "Q6") (pin "1") (pinfunction "S1_1") (pintype "passive"))
      (node (ref "Q6") (pin "3") (pinfunction "S2_3") (pintype "passive"))
      (node (ref "U3") (pin "11") (pinfunction "VBUS_A_11") (pintype "passive"))
    )
    (net (code "34") (name "/VBUS_C") (class "Default")
      (node (ref "C19") (pin "2") (pinfunction "2_2") (pintype "passive"))
      (node (ref "J4") (pin "A4") (pinfunction "VBUS1_A4") (pintype "passive"))
      (node (ref "J4") (pin "A9") (pinfunction "VBUS2_A9") (pintype "passive"))
      (node (ref "J4") (pin "B4") (pinfunction "VBUS3_B4") (pintype "passive"))
      (node (ref "J4") (pin "B9") (pinfunction "VBUS4_B9") (pintype "passive"))
      (node (ref "Q8") (pin "1") (pinfunction "S1_1") (pintype "passive"))
      (node (ref "Q8") (pin "3") (pinfunction "S2_3") (pintype "passive"))
      (node (ref "U3") (pin "10") (pinfunction "VBUS_C_10") (pintype "passive"))
    )
    (net (code "35") (name "/VCC") (class "Default")
      (node (ref "C20") (pin "2") (pinfunction "2_2") (pintype "passive"))
      (node (ref "D3") (pin "1") (pintype "passive"))
      (node (ref "Q12") (pin "3") (pinfunction "D_3") (pintype "passive"))
      (node (ref "R27") (pin "1") (pinfunction "1_1") (pintype "passive"))
      (node (ref "U3") (pin "18") (pinfunction "VCC_18") (pintype "passive"))
      (node (ref "ZD3") (pin "2") (pinfunction "K_2") (pintype "passive"))
    )
    (net (code "36") (name "/VDRV") (class "Default")
      (node (ref "C15") (pin "2") (pinfunction "2_2") (pintype "passive"))
      (node (ref "U3") (pin "8") (pinfunction "VDRV_8") (pintype "passive"))
    )
    (net (code "37") (name "/VMCU") (class "Default")
      (node (ref "C21") (pin "1") (pinfunction "1_1") (pintype "passive"))
      (node (ref "R15") (pin "1") (pinfunction "1_1") (pintype "passive"))
      (node (ref "R19") (pin "1") (pinfunction "1_1") (pintype "passive"))
      (node (ref "R20") (pin "1") (pinfunction "1_1") (pintype "passive"))
      (node (ref "R21") (pin "1") (pinfunction "1_1") (pintype "passive"))
      (node (ref "U4") (pin "16") (pinfunction "VDD_16") (pintype "passive"))
    )
    (net (code "38") (name "/VOUT") (class "Default")
      (node (ref "C11") (pin "2") (pinfunction "2_2") (pintype "passive"))
      (node (ref "C12") (pin "2") (pinfunction "2_2") (pintype "passive"))
      (node (ref "C13") (pin "2") (pinfunction "2_2") (pintype "passive"))
      (node (ref "C14") (pin "2") (pinfunction "2_2") (pintype "passive"))
      (node (ref "Q5") (pin "5") (pinfunction "D2_5") (pintype "passive"))
      (node (ref "Q6") (pin "5") (pinfunction "D2_5") (pintype "passive"))
      (node (ref "Q8") (pin "5") (pinfunction "D2_5") (pintype "passive"))
      (node (ref "U3") (pin "12") (pinfunction "VOUT_A_12") (pintype "passive"))
      (node (ref "U3") (pin "25") (pinfunction "VOUT1_25") (pintype "passive"))
      (node (ref "U3") (pin "26") (pinfunction "VOUT2_26") (pintype "passive"))
      (node (ref "U3") (pin "27") (pinfunction "VOUT3_27") (pintype "passive"))
      (node (ref "U3") (pin "28") (pinfunction "VOUT4_28") (pintype "passive"))
      (node (ref "U3") (pin "29") (pinfunction "VOUT5_29") (pintype "passive"))
      (node (ref "U3") (pin "9") (pinfunction "VOUT_C_9") (pintype "passive"))
    )
    (net (code "39") (name "/WLED{slash}DATA") (class "Default")
      (node (ref "R14") (pin "2") (pinfunction "2_2") (pintype "passive"))
      (node (ref "U3") (pin "20") (pinfunction "WLED/DATA_20") (pintype "passive"))
    )
    (net (code "40") (name "B+") (class "Default")
      (node (ref "C5") (pin "1") (pinfunction "1_1") (pintype "passive"))
      (node (ref "C6") (pin "1") (pinfunction "1_1") (pintype "passive"))
      (node (ref "C8") (pin "2") (pinfunction "2_2") (pintype "passive"))
      (node (ref "D2") (pin "1") (pinfunction "A_1") (pintype "passive"))
      (node (ref "D3") (pin "2") (pintype "passive"))
      (node (ref "R1") (pin "2") (pinfunction "2_2") (pintype "passive"))
      (node (ref "R5") (pin "1") (pinfunction "1_1") (pintype "passive"))
      (node (ref "TP1") (pin "1") (pinfunction "1_1") (pintype "passive"))
      (node (ref "U3") (pin "15") (pinfunction "BAT_15") (pintype "passive"))
    )
    (net (code "41") (name "B-") (class "Default")
      (node (ref "C1") (pin "1") (pinfunction "1_1") (pintype "passive"))
      (node (ref "Q1") (pin "1") (pinfunction "S1_1") (pintype "passive"))
      (node (ref "Q2") (pin "1") (pinfunction "S1_1") (pintype "passive"))
      (node (ref "Q3") (pin "1") (pinfunction "S1_1") (pintype "passive"))
      (node (ref "Q4") (pin "1") (pinfunction "S1_1") (pintype "passive"))
      (node (ref "TP2") (pin "1") (pinfunction "1_1") (pintype "passive"))
      (node (ref "U1") (pin "6") (pinfunction "GND_6") (pintype "passive"))
    )
    (net (code "42") (name "GND") (class "Default")
      (node (ref "C11") (pin "1") (pinfunction "1_1") (pintype "passive"))
      (node (ref "C12") (pin "1") (pinfunction "1_1") (pintype "passive"))
      (node (ref "C13") (pin "1") (pinfunction "1_1") (pintype "passive"))
      (node (ref "C14") (pin "1") (pinfunction "1_1") (pintype "passive"))
      (node (ref "C15") (pin "1") (pinfunction "1_1") (pintype "passive"))
      (node (ref "C19") (pin "1") (pinfunction "1_1") (pintype "passive"))
      (node (ref "C2") (pin "2") (pinfunction "2_2") (pintype "passive"))
      (node (ref "C20") (pin "1") (pinfunction "1_1") (pintype "passive"))
      (node (ref "C21") (pin "2") (pinfunction "2_2") (pintype "passive"))
      (node (ref "C22") (pin "1") (pinfunction "1_1") (pintype "passive"))
      (node (ref "C23") (pin "1") (pinfunction "1_1") (pintype "passive"))
      (node (ref "C24") (pin "1") (pinfunction "1_1") (pintype "passive"))
      (node (ref "C3") (pin "2") (pinfunction "2_2") (pintype "passive"))
      (node (ref "C4") (pin "1") (pinfunction "1_1") (pintype "passive"))
      (node (ref "C7") (pin "1") (pinfunction "1_1") (pintype "passive"))
      (node (ref "C8") (pin "1") (pinfunction "1_1") (pintype "passive"))
      (node (ref "C9") (pin "1") (pinfunction "1_1") (pintype "passive"))
      (node (ref "D1") (pin "2") (pinfunction "K_2") (pintype "passive"))
      (node (ref "J1") (pin "4") (pinfunction "ID_4") (pintype "passive"))
      (node (ref "J1") (pin "5") (pinfunction "GND_5") (pintype "passive"))
      (node (ref "J1") (pin "6") (pinfunction "SHIELD1_6") (pintype "passive"))
      (node (ref "J1") (pin "7") (pinfunction "SHIELD2_7") (pintype "passive"))
      (node (ref "J1") (pin "8") (pinfunction "SHIELD3_8") (pintype "passive"))
      (node (ref "J1") (pin "9") (pinfunction "SHIELD4_9") (pintype "passive"))
      (node (ref "J2") (pin "4") (pinfunction "GND_4") (pintype "passive"))
      (node (ref "J2") (pin "5") (pinfunction "SHIELD1_5") (pintype "passive"))
      (node (ref "J2") (pin "6") (pinfunction "SHIELD2_6") (pintype "passive"))
      (node (ref "J4") (pin "A1") (pinfunction "GND1_A1") (pintype "passive"))
      (node (ref "J4") (pin "A12") (pinfunction "GND2_A12") (pintype "passive"))
      (node (ref "J4") (pin "B1") (pinfunction "GND3_B1") (pintype "passive"))
      (node (ref "J4") (pin "B12") (pinfunction "GND4_B12") (pintype "passive"))
      (node (ref "J4") (pin "C1") (pinfunction "SHIELD1_C1") (pintype "passive"))
      (node (ref "J4") (pin "C2") (pinfunction "SHIELD2_C2") (pintype "passive"))
      (node (ref "J4") (pin "C3") (pinfunction "SHIELD3_C3") (pintype "passive"))
      (node (ref "J4") (pin "C4") (pinfunction "SHIELD4_C4") (pintype "passive"))
      (node (ref "Q1") (pin "3") (pinfunction "S2_3") (pintype "passive"))
      (node (ref "Q2") (pin "3") (pinfunction "S2_3") (pintype "passive"))
      (node (ref "Q3") (pin "3") (pinfunction "S2_3") (pintype "passive"))
      (node (ref "Q4") (pin "3") (pinfunction "S2_3") (pintype "passive"))
      (node (ref "Q7") (pin "2") (pinfunction "E_2") (pintype "passive"))
      (node (ref "Q9") (pin "1") (pinfunction "S1_1") (pintype "passive"))
      (node (ref "R12") (pin "1") (pinfunction "1_1") (pintype "passive"))
      (node (ref "R2") (pin "1") (pinfunction "1_1") (pintype "passive"))
      (node (ref "R28") (pin "1") (pinfunction "1_1") (pintype "passive"))
      (node (ref "R31") (pin "2") (pinfunction "2_2") (pintype "passive"))
      (node (ref "R33") (pin "2") (pinfunction "2_2") (pintype "passive"))
      (node (ref "R6") (pin "2") (pinfunction "2_2") (pintype "passive"))
      (node (ref "R7") (pin "1") (pinfunction "1_1") (pintype "passive"))
      (node (ref "S1") (pin "2") (pinfunction "2_2") (pintype "passive"))
      (node (ref "U3") (pin "13") (pinfunction "AGND_13") (pintype "passive"))
      (node (ref "U3") (pin "24") (pinfunction "LED4/I2C_24") (pintype "passive"))
      (node (ref "U3") (pin "41") (pinfunction "EPAD_41") (pintype "passive"))
      (node (ref "U4") (pin "1") (pinfunction "VSS_1") (pintype "passive"))
      (node (ref "ZD3") (pin "1") (pinfunction "A_1") (pintype "passive"))
    )
    (net (code "43") (name "Net-(C17-Pad2)") (class "Default")
      (node (ref "C17") (pin "2") (pinfunction "2_2") (pintype "passive"))
      (node (ref "R10") (pin "2") (pinfunction "2_2") (pintype "passive"))
    )
    (net (code "44") (name "Net-(D1-A)") (class "Default")
      (node (ref "D1") (pin "1") (pinfunction "A_1") (pintype "passive"))
      (node (ref "R13") (pin "1") (pinfunction "1_1") (pintype "passive"))
    )
    (net (code "45") (name "Net-(D2-K)") (class "Default")
      (node (ref "D2") (pin "2") (pinfunction "K_2") (pintype "passive"))
      (node (ref "R14") (pin "1") (pinfunction "1_1") (pintype "passive"))
    )
    (net (code "46") (name "Net-(D3-Pad3)") (class "Default")
      (node (ref "D3") (pin "3") (pintype "passive"))
      (node (ref "R15") (pin "2") (pinfunction "2_2") (pintype "passive"))
    )
    (net (code "47") (name "Net-(J5-DM)") (class "Default")
      (node (ref "J5") (pin "2") (pinfunction "DM_2") (pintype "passive"))
      (node (ref "J5") (pin "3") (pinfunction "DP_3") (pintype "passive"))
    )
    (net (code "48") (name "Net-(J5-GND)") (class "Default")
      (node (ref "J5") (pin "4") (pinfunction "GND_4") (pintype "passive"))
      (node (ref "R16") (pin "2") (pinfunction "2_2") (pintype "passive"))
      (node (ref "R28") (pin "2") (pinfunction "2_2") (pintype "passive"))
    )
    (net (code "49") (name "Net-(J5-VBUS)") (class "Default")
      (node (ref "C22") (pin "2") (pinfunction "2_2") (pintype "passive"))
      (node (ref "J5") (pin "1") (pinfunction "VBUS_1") (pintype "passive"))
      (node (ref "Q10") (pin "3") (pinfunction "D_3") (pintype "passive"))
      (node (ref "R17") (pin "1") (pinfunction "1_1") (pintype "passive"))
      (node (ref "R18") (pin "2") (pinfunction "2_2") (pintype "passive"))
    )
    (net (code "50") (name "Net-(J6-Pad1)") (class "Default")
      (node (ref "J6") (pin "1") (pinfunction "1_1") (pintype "passive"))
      (node (ref "R23") (pin "1") (pinfunction "1_1") (pintype "passive"))
    )
    (net (code "51") (name "Net-(J6-Pad2)") (class "Default")
      (node (ref "J6") (pin "2") (pinfunction "2_2") (pintype "passive"))
      (node (ref "R24") (pin "1") (pinfunction "1_1") (pintype "passive"))
    )
    (net (code "52") (name "Net-(J6-Pad3)") (class "Default")
      (node (ref "J6") (pin "3") (pinfunction "3_3") (pintype "passive"))
      (node (ref "R25") (pin "1") (pinfunction "1_1") (pintype "passive"))
    )
    (net (code "53") (name "Net-(J6-Pad4)") (class "Default")
      (node (ref "J6") (pin "4") (pinfunction "4_4") (pintype "passive"))
      (node (ref "R26") (pin "1") (pinfunction "1_1") (pintype "passive"))
    )
    (net (code "54") (name "Net-(J6-Pad5)") (class "Default")
      (node (ref "J6") (pin "5") (pinfunction "5_5") (pintype "passive"))
      (node (ref "R29") (pin "1") (pinfunction "1_1") (pintype "passive"))
    )
    (net (code "55") (name "Net-(J6-Pad6)") (class "Default")
      (node (ref "J6") (pin "6") (pinfunction "6_6") (pintype "passive"))
      (node (ref "R30") (pin "1") (pinfunction "1_1") (pintype "passive"))
    )
    (net (code "56") (name "Net-(Q1-D1)") (class "Default")
      (node (ref "Q1") (pin "2") (pinfunction "D1_2") (pintype "passive"))
      (node (ref "Q2") (pin "5") (pinfunction "D2_5") (pintype "passive"))
    )
    (net (code "57") (name "Net-(Q1-G1)") (class "Default")
      (node (ref "Q1") (pin "6") (pinfunction "G1_6") (pintype "passive"))
      (node (ref "Q2") (pin "6") (pinfunction "G1_6") (pintype "passive"))
      (node (ref "Q3") (pin "6") (pinfunction "G1_6") (pintype "passive"))
      (node (ref "Q4") (pin "6") (pinfunction "G1_6") (pintype "passive"))
      (node (ref "U1") (pin "1") (pinfunction "OD_1") (pintype "passive"))
    )
    (net (code "58") (name "Net-(Q1-G2)") (class "Default")
      (node (ref "Q1") (pin "4") (pinfunction "G2_4") (pintype "passive"))
      (node (ref "Q2") (pin "4") (pinfunction "G2_4") (pintype "passive"))
      (node (ref "Q3") (pin "4") (pinfunction "G2_4") (pintype "passive"))
      (node (ref "Q4") (pin "4") (pinfunction "G2_4") (pintype "passive"))
      (node (ref "U1") (pin "3") (pinfunction "OC_3") (pintype "passive"))
    )
    (net (code "59") (name "Net-(Q2-D1)") (class "Default")
      (node (ref "Q2") (pin "2") (pinfunction "D1_2") (pintype "passive"))
      (node (ref "Q3") (pin "5") (pinfunction "D2_5") (pintype "passive"))
    )
    (net (code "60") (name "Net-(Q3-D1)") (class "Default")
      (node (ref "Q3") (pin "2") (pinfunction "D1_2") (pintype "passive"))
      (node (ref "Q4") (pin "5") (pinfunction "D2_5") (pintype "passive"))
    )
    (net (code "61") (name "Net-(Q7-B)") (class "Default")
      (node (ref "Q7") (pin "1") (pinfunction "B_1") (pintype "passive"))
      (node (ref "R4") (pin "2") (pinfunction "2_2") (pintype "passive"))
      (node (ref "R6") (pin "1") (pinfunction "1_1") (pintype "passive"))
    )
    (net (code "62") (name "Net-(Q7-C)") (class "Default")
      (node (ref "Q7") (pin "3") (pinfunction "C_3") (pintype "passive"))
      (node (ref "Q9") (pin "6") (pinfunction "G1_6") (pintype "passive"))
      (node (ref "R3") (pin "2") (pinfunction "2_2") (pintype "passive"))
    )
    (net (code "63") (name "Net-(Q9-D1)") (class "Default")
      (node (ref "Q9") (pin "2") (pinfunction "D1_2") (pintype "passive"))
      (node (ref "Q9") (pin "5") (pinfunction "D2_5") (pintype "passive"))
    )
    (net (code "64") (name "Net-(Q9-G2)") (class "Default")
      (node (ref "C18") (pin "1") (pinfunction "1_1") (pintype "passive"))
      (node (ref "Q9") (pin "4") (pinfunction "G2_4") (pintype "passive"))
      (node (ref "U2") (pin "1") (pinfunction "GATE_1") (pintype "passive"))
    )
    (net (code "65") (name "Net-(Q9-S2)") (class "Default")
      (node (ref "C16") (pin "1") (pinfunction "1_1") (pintype "passive"))
      (node (ref "C17") (pin "1") (pinfunction "1_1") (pintype "passive"))
      (node (ref "C18") (pin "2") (pinfunction "2_2") (pintype "passive"))
      (node (ref "J3") (pin "1") (pinfunction "1_1") (pintype "passive"))
      (node (ref "J3") (pin "10") (pinfunction "10_10") (pintype "passive"))
      (node (ref "J3") (pin "2") (pinfunction "2_2") (pintype "passive"))
      (node (ref "Q9") (pin "3") (pinfunction "S2_3") (pintype "passive"))
      (node (ref "R11") (pin "2") (pinfunction "2_2") (pintype "passive"))
      (node (ref "U2") (pin "2") (pinfunction "GND_2") (pintype "passive"))
      (node (ref "ZD2") (pin "1") (pinfunction "A_1") (pintype "passive"))
    )
    (net (code "66") (name "Net-(Q10-G)") (class "Default")
      (node (ref "Q10") (pin "1") (pinfunction "G_1") (pintype "passive"))
      (node (ref "Q11") (pin "3") (pinfunction "D_3") (pintype "passive"))
      (node (ref "Q12") (pin "1") (pinfunction "G_1") (pintype "passive"))
      (node (ref "R31") (pin "1") (pinfunction "1_1") (pintype "passive"))
    )
    (net (code "67") (name "Net-(Q11-G)") (class "Default")
      (node (ref "Q11") (pin "1") (pinfunction "G_1") (pintype "passive"))
      (node (ref "R27") (pin "2") (pinfunction "2_2") (pintype "passive"))
      (node (ref "R33") (pin "1") (pinfunction "1_1") (pintype "passive"))
    )
    (net (code "68") (name "Net-(Q12-S)") (class "Default")
      (node (ref "Q12") (pin "2") (pinfunction "S_2") (pintype "passive"))
      (node (ref "R17") (pin "2") (pinfunction "2_2") (pintype "passive"))
    )
    (net (code "69") (name "Net-(U1-CS)") (class "Default")
      (node (ref "R2") (pin "2") (pinfunction "2_2") (pintype "passive"))
      (node (ref "U1") (pin "2") (pinfunction "CS_2") (pintype "passive"))
    )
    (net (code "70") (name "Net-(U1-VCC)") (class "Default")
      (node (ref "C1") (pin "2") (pinfunction "2_2") (pintype "passive"))
      (node (ref "R1") (pin "1") (pinfunction "1_1") (pintype "passive"))
      (node (ref "U1") (pin "5") (pinfunction "VCC_5") (pintype "passive"))
    )
    (net (code "71") (name "Net-(U2-VDD)") (class "Default")
      (node (ref "C16") (pin "2") (pinfunction "2_2") (pintype "passive"))
      (node (ref "R11") (pin "1") (pinfunction "1_1") (pintype "passive"))
      (node (ref "R8") (pin "1") (pinfunction "1_1") (pintype "passive"))
      (node (ref "R9") (pin "2") (pinfunction "2_2") (pintype "passive"))
      (node (ref "U2") (pin "5") (pinfunction "VDD_5") (pintype "passive"))
      (node (ref "ZD2") (pin "2") (pinfunction "K_2") (pintype "passive"))
    )
    (net (code "72") (name "Net-(ZD1-A)") (class "Default")
      (node (ref "R4") (pin "1") (pinfunction "1_1") (pintype "passive"))
      (node (ref "ZD1") (pin "1") (pinfunction "A_1") (pintype "passive"))
    )
    (net (code "73") (name "VBUS_B") (class "Default")
      (node (ref "C4") (pin "2") (pinfunction "2_2") (pintype "passive"))
      (node (ref "J1") (pin "1") (pinfunction "VBUS_1") (pintype "passive"))
      (node (ref "J3") (pin "6") (pinfunction "6_6") (pintype "passive"))
      (node (ref "Q5") (pin "1") (pinfunction "S1_1") (pintype "passive"))
      (node (ref "Q5") (pin "3") (pinfunction "S2_3") (pintype "passive"))
      (node (ref "R10") (pin "1") (pinfunction "1_1") (pintype "passive"))
      (node (ref "R3") (pin "1") (pinfunction "1_1") (pintype "passive"))
      (node (ref "R9") (pin "1") (pinfunction "1_1") (pintype "passive"))
      (node (ref "U3") (pin "30") (pinfunction "VBUS_B_30") (pintype "passive"))
      (node (ref "ZD1") (pin "2") (pinfunction "K_2") (pintype "passive"))
    )
    (net (code "74") (name "unconnected-(J3-Pad3)") (class "Default")
      (node (ref "J3") (pin "3") (pinfunction "3_3") (pintype "passive"))
    )
    (net (code "75") (name "unconnected-(J3-Pad4)") (class "Default")
      (node (ref "J3") (pin "4") (pinfunction "4_4") (pintype "passive"))
    )
    (net (code "76") (name "unconnected-(J3-Pad7)") (class "Default")
      (node (ref "J3") (pin "7") (pinfunction "7_7") (pintype "passive"))
    )
    (net (code "77") (name "unconnected-(J3-Pad8)") (class "Default")
      (node (ref "J3") (pin "8") (pinfunction "8_8") (pintype "passive"))
    )
    (net (code "78") (name "unconnected-(J4-SBU1-PadA8)") (class "Default")
      (node (ref "J4") (pin "A8") (pinfunction "SBU1_A8") (pintype "passive"))
    )
    (net (code "79") (name "unconnected-(J4-SBU2-PadB8)") (class "Default")
      (node (ref "J4") (pin "B8") (pinfunction "SBU2_B8") (pintype "passive"))
    )
    (net (code "80") (name "unconnected-(J4-SSRXn1-PadB10)") (class "Default")
      (node (ref "J4") (pin "B10") (pinfunction "SSRXn1_B10") (pintype "passive"))
    )
    (net (code "81") (name "unconnected-(J4-SSRXn2-PadA10)") (class "Default")
      (node (ref "J4") (pin "A10") (pinfunction "SSRXn2_A10") (pintype "passive"))
    )
    (net (code "82") (name "unconnected-(J4-SSRXp1-PadB11)") (class "Default")
      (node (ref "J4") (pin "B11") (pinfunction "SSRXp1_B11") (pintype "passive"))
    )
    (net (code "83") (name "unconnected-(J4-SSRXp2-PadA11)") (class "Default")
      (node (ref "J4") (pin "A11") (pinfunction "SSRXp2_A11") (pintype "passive"))
    )
    (net (code "84") (name "unconnected-(J4-SSTXn1-PadA3)") (class "Default")
      (node (ref "J4") (pin "A3") (pinfunction "SSTXn1_A3") (pintype "passive"))
    )
    (net (code "85") (name "unconnected-(J4-SSTXn2-PadB3)") (class "Default")
      (node (ref "J4") (pin "B3") (pinfunction "SSTXn2_B3") (pintype "passive"))
    )
    (net (code "86") (name "unconnected-(J4-SSTXp1-PadA2)") (class "Default")
      (node (ref "J4") (pin "A2") (pinfunction "SSTXp1_A2") (pintype "passive"))
    )
    (net (code "87") (name "unconnected-(J4-SSTXp2-PadB2)") (class "Default")
      (node (ref "J4") (pin "B2") (pinfunction "SSTXp2_B2") (pintype "passive"))
    )
    (net (code "88") (name "unconnected-(J5-SHIELD1-Pad5)") (class "Default")
      (node (ref "J5") (pin "5") (pinfunction "SHIELD1_5") (pintype "passive"))
    )
    (net (code "89") (name "unconnected-(J5-SHIELD2-Pad6)") (class "Default")
      (node (ref "J5") (pin "6") (pinfunction "SHIELD2_6") (pintype "passive"))
    )
    (net (code "90") (name "unconnected-(Q1-D2-Pad5)") (class "Default")
      (node (ref "Q1") (pin "5") (pinfunction "D2_5") (pintype "passive"))
    )
    (net (code "91") (name "unconnected-(Q4-D1-Pad2)") (class "Default")
      (node (ref "Q4") (pin "2") (pinfunction "D1_2") (pintype "passive"))
    )
    (net (code "92") (name "unconnected-(Q5-D1-Pad2)") (class "Default")
      (node (ref "Q5") (pin "2") (pinfunction "D1_2") (pintype "passive"))
    )
    (net (code "93") (name "unconnected-(Q6-D1-Pad2)") (class "Default")
      (node (ref "Q6") (pin "2") (pinfunction "D1_2") (pintype "passive"))
    )
    (net (code "94") (name "unconnected-(Q8-D1-Pad2)") (class "Default")
      (node (ref "Q8") (pin "2") (pinfunction "D1_2") (pintype "passive"))
    )
    (net (code "95") (name "unconnected-(U1-TD-Pad4)") (class "Default")
      (node (ref "U1") (pin "4") (pinfunction "TD_4") (pintype "passive"))
    )
    (net (code "96") (name "unconnected-(U2-NC1-Pad3)") (class "Default")
      (node (ref "U2") (pin "3") (pinfunction "NC1_3") (pintype "passive"))
    )
    (net (code "97") (name "unconnected-(U2-NC2-Pad4)") (class "Default")
      (node (ref "U2") (pin "4") (pinfunction "NC2_4") (pintype "passive"))
    )
    (net (code "98") (name "unconnected-(U4-PA2-Pad4)") (class "Default")
      (node (ref "U4") (pin "4") (pinfunction "PA2_4") (pintype "passive"))
    )
    (net (code "99") (name "unconnected-(U4-PB3-Pad9)") (class "Default")
      (node (ref "U4") (pin "9") (pinfunction "PB3_9") (pintype "passive"))
    )
  )
)
